# Proximidad.net
KiCad netlist of a schematic drawn in Altium Designer
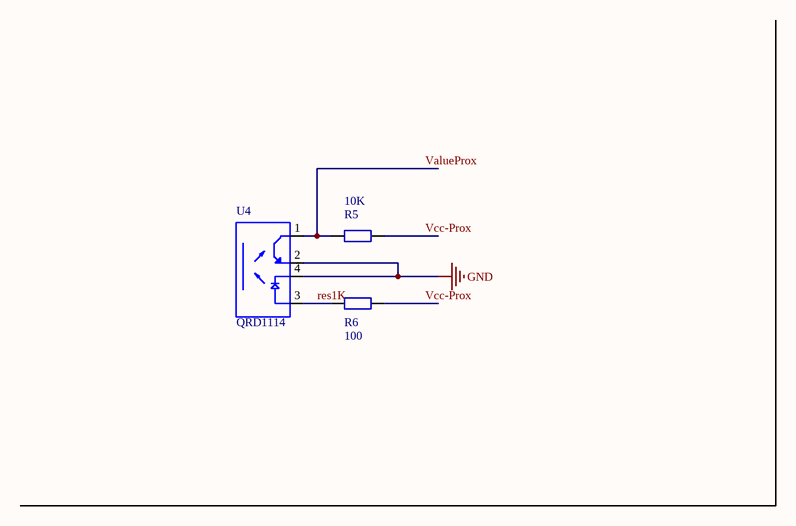
[diagram p0: Proximidad.SchDoc]

(export (version "E")
  (design (tool "Eeschema 10.0.6"))
  (components
    (comp (ref "R5")
      (value "10K")
      (footprint "R1206-0.55")
      (description "Resistor, generic")
      (fields (field (name "Comment") "R"))
      (libsource (lib "IFS_Altium") (part "R"))
    )
    (comp (ref "R6")
      (value "100")
      (footprint "R1206-0.55")
      (description "Resistor, generic")
      (fields (field (name "Comment") "R"))
      (libsource (lib "IFS_Altium") (part "R"))
    )
    (comp (ref "U4")
      (value "QRD1114")
      (footprint "*ONS_QRD1114")
      (description "Sensor 贸ptico reflectante 0.050 _1.27 mm_ radial - 4 conductores")
      (fields (field (name "DIGI-KEY_PART_NUMBER") "QRD1114-ND") (field (name "MF") "ON Semiconductor"))
      (libsource (lib "QRD1114") (part "QRD1114"))
    )
  )
  (nets
    (net (code "1") (name "/ValueProx") (class "Default")
      (node (ref "R5") (pin "1") (pinfunction "1_1") (pintype "passive"))
      (node (ref "U4") (pin "1") (pinfunction "CT_1") (pintype "passive"))
    )
    (net (code "2") (name "/Vcc-Prox") (class "Default")
      (node (ref "R5") (pin "2") (pinfunction "2_2") (pintype "passive"))
      (node (ref "R6") (pin "2") (pinfunction "2_2") (pintype "passive"))
    )
    (net (code "3") (name "/res1K") (class "Default")
      (node (ref "R6") (pin "1") (pinfunction "1_1") (pintype "passive"))
      (node (ref "U4") (pin "3") (pinfunction "A_3") (pintype "passive"))
    )
    (net (code "4") (name "GND") (class "Default")
      (node (ref "U4") (pin "2") (pinfunction "ET_2") (pintype "passive"))
      (node (ref "U4") (pin "4") (pinfunction "C_4") (pintype "passive"))
    )
  )
)
